# Sheet1.net
KiCad netlist of a schematic drawn in Altium Designer
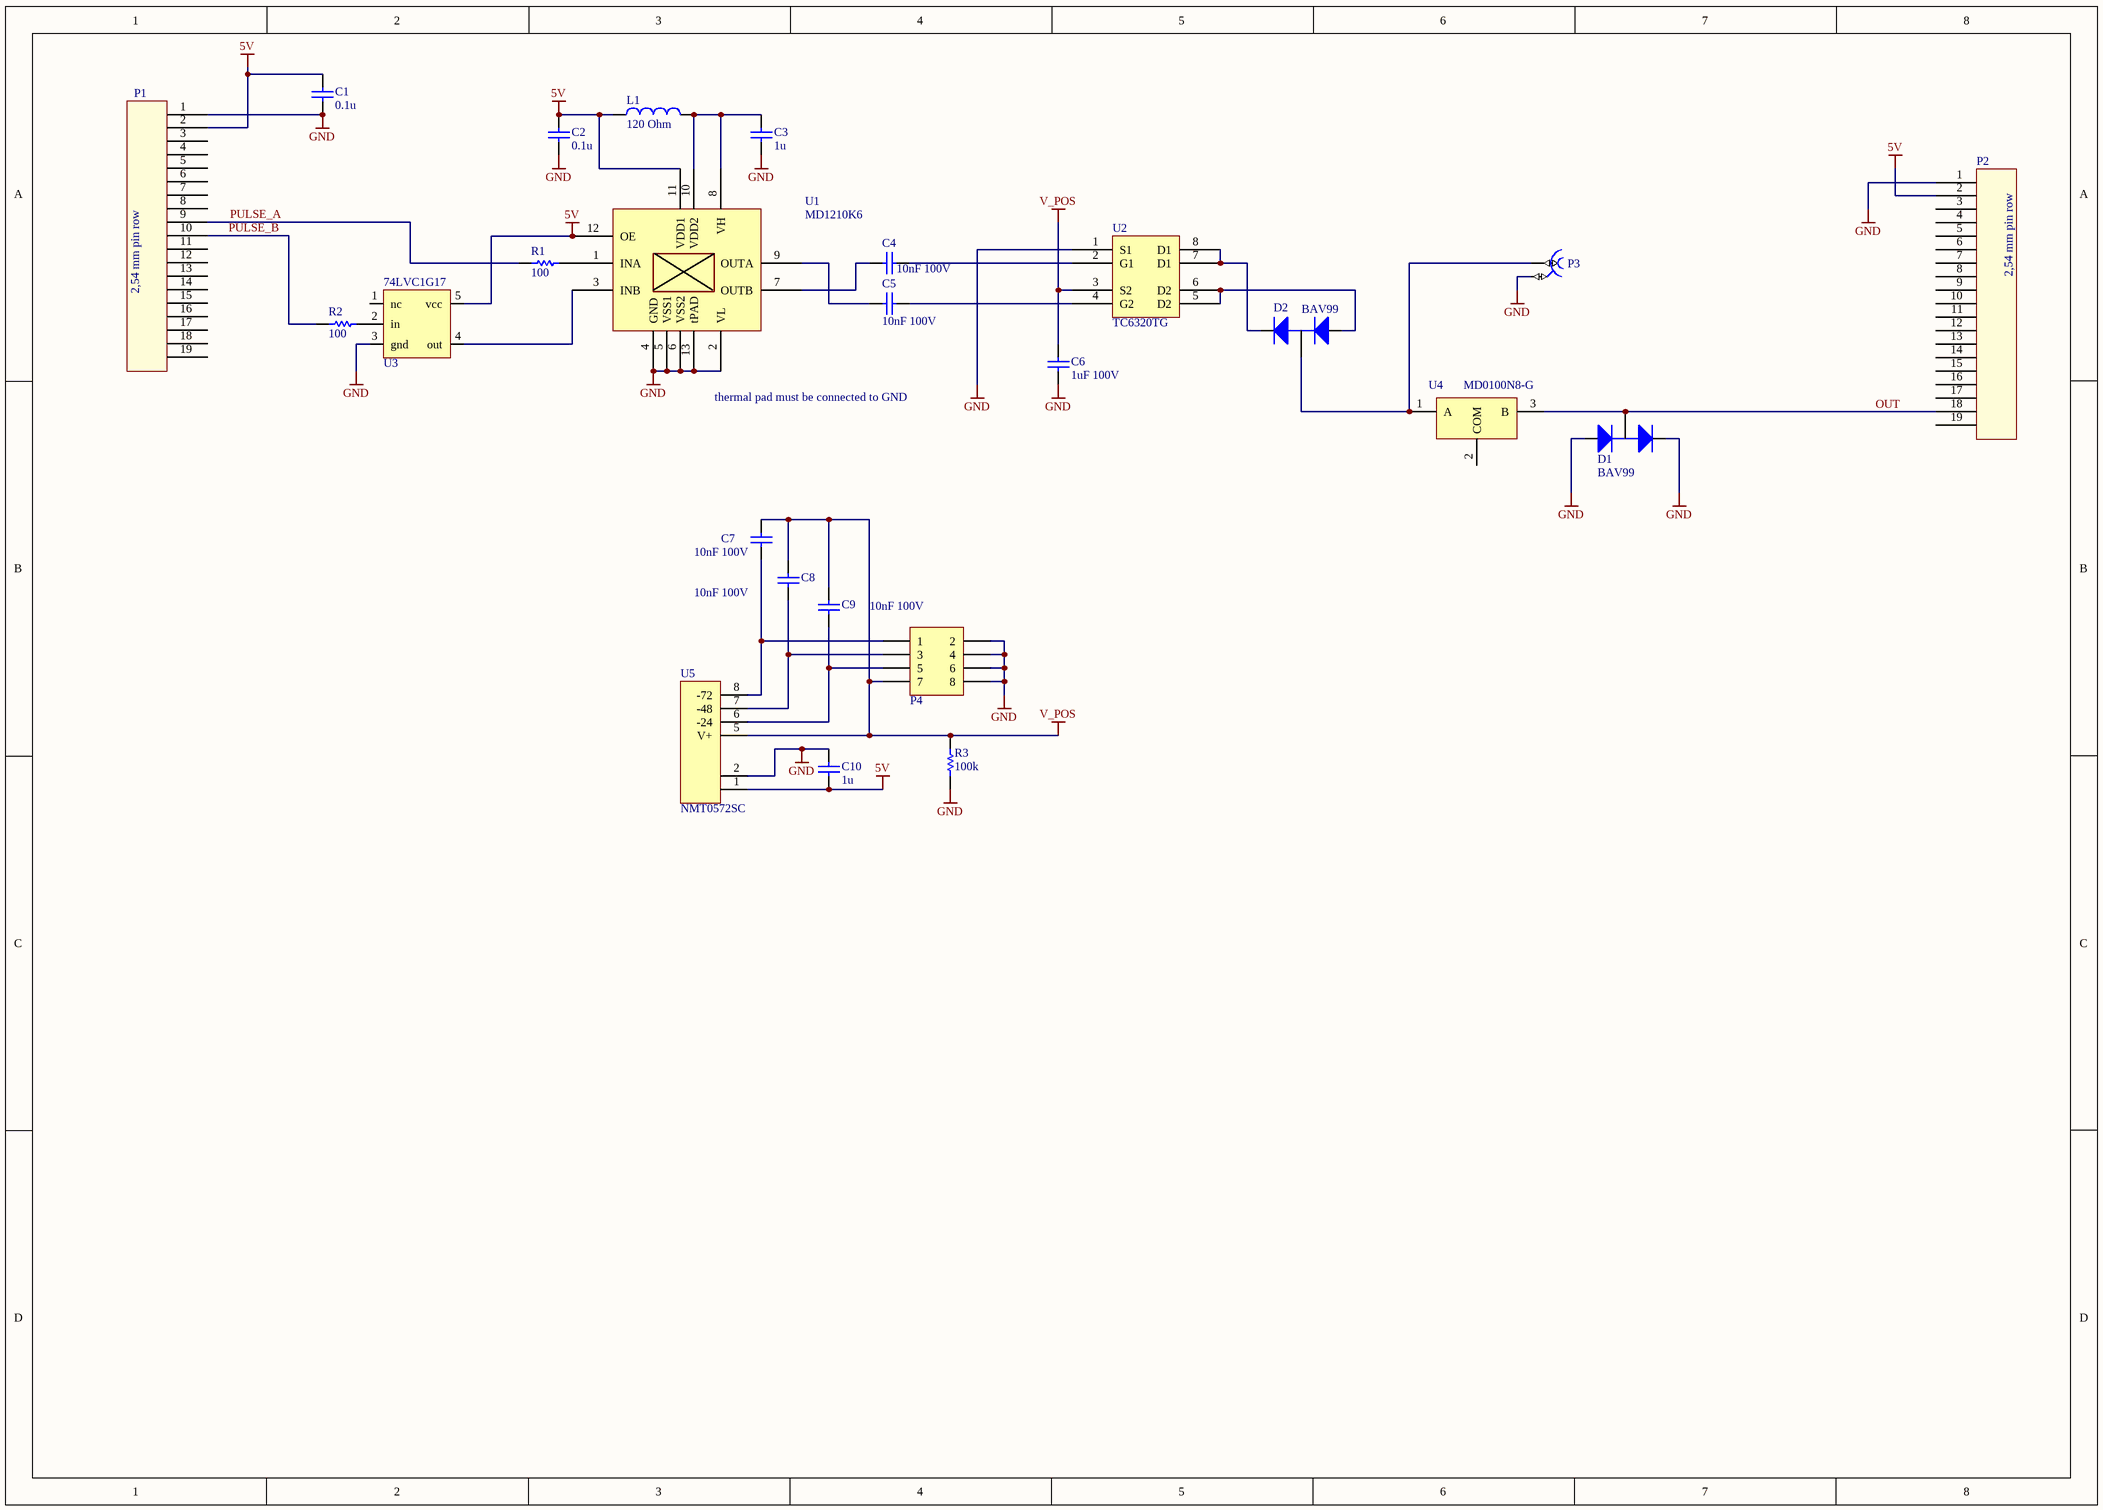
[diagram p0: Sheet1.SchDoc]

(export (version "E")
  (design (tool "Eeschema 10.0.6"))
  (components
    (comp (ref "C1")
      (value "0.1u")
      (footprint "0603RC")
      (description "Capacitor")
      (fields (field (name "PUBLISHER") "Altium Limited"))
      (libsource (lib "Miscellaneous Devices") (part "Cap"))
    )
    (comp (ref "C2")
      (value "0.1u")
      (footprint "0603RC")
      (description "Capacitor")
      (fields (field (name "PUBLISHER") "Altium Limited"))
      (libsource (lib "Miscellaneous Devices") (part "Cap"))
    )
    (comp (ref "C3")
      (value "1u")
      (footprint "0805RC")
      (description "Capacitor")
      (fields (field (name "PUBLISHER") "Altium Limited"))
      (libsource (lib "Miscellaneous Devices") (part "Cap"))
    )
    (comp (ref "C4")
      (value "10nF 100V")
      (footprint "0805RC")
      (description "Capacitor")
      (fields (field (name "PUBLISHER") "Altium Limited"))
      (libsource (lib "Miscellaneous Devices") (part "Cap"))
    )
    (comp (ref "C5")
      (value "10nF 100V")
      (footprint "0805RC")
      (description "Capacitor")
      (fields (field (name "PUBLISHER") "Altium Limited"))
      (libsource (lib "Miscellaneous Devices") (part "Cap"))
    )
    (comp (ref "C6")
      (value "1uF 100V")
      (footprint "1206RC")
      (description "Capacitor")
      (fields (field (name "PUBLISHER") "Altium Limited"))
      (libsource (lib "Miscellaneous Devices") (part "Cap"))
    )
    (comp (ref "C7")
      (value "10nF 100V")
      (footprint "0805RC")
      (description "Capacitor")
      (fields (field (name "PUBLISHER") "Altium Limited"))
      (libsource (lib "Miscellaneous Devices") (part "Cap"))
    )
    (comp (ref "C8")
      (value "10nF 100V")
      (footprint "0805RC")
      (description "Capacitor")
      (fields (field (name "PUBLISHER") "Altium Limited"))
      (libsource (lib "Miscellaneous Devices") (part "Cap"))
    )
    (comp (ref "C9")
      (value "10nF 100V")
      (footprint "0805RC")
      (description "Capacitor")
      (fields (field (name "PUBLISHER") "Altium Limited"))
      (libsource (lib "Miscellaneous Devices") (part "Cap"))
    )
    (comp (ref "C10")
      (value "1u")
      (footprint "0805RC")
      (description "Capacitor")
      (fields (field (name "PUBLISHER") "Altium Limited"))
      (libsource (lib "Miscellaneous Devices") (part "Cap"))
    )
    (comp (ref "D1")
      (value "BAV99")
      (footprint "SOT-23")
      (description "Medium-speed Switching Double Diode with Low Leakage Current")
      (fields (field (name "PUBLISHER") "Altium Limited"))
      (libsource (lib "Miscellaneous Devices") (part "BAV199"))
    )
    (comp (ref "D2")
      (value "BAV99")
      (footprint "SOT-23")
      (description "Medium-speed Switching Double Diode with Low Leakage Current")
      (fields (field (name "PUBLISHER") "Altium Limited"))
      (libsource (lib "Miscellaneous Devices") (part "BAV199"))
    )
    (comp (ref "L1")
      (value "120 Ohm")
      (footprint "0805R")
      (description "Inductor")
      (fields (field (name "Comment") "BLM21PG121SN1D") (field (name "PUBLISHER") "Altium Limited"))
      (libsource (lib "Miscellaneous Devices") (part "Inductor"))
    )
    (comp (ref "P1")
      (value "PLS_2.54mm-19")
      (footprint "PLS_2.54mm-19")
      (libsource (lib "") (part "PLS_2.54mm-19_1"))
    )
    (comp (ref "P2")
      (value "PLS_2.54mm-19")
      (footprint "PLS_2.54mm-19")
      (libsource (lib "alt_vovan") (part "PLS_2.54mm-19"))
    )
    (comp (ref "P3")
      (value "SMA")
      (footprint "echOpen_ADC_Card:AMPHENOL_132357-11")
      (fields
        (field (name "PART NUMBER") "AMPHENOL_132357-11")
        (field (name "MANUFACTURER") "AMPHENOL")
        (field (name "MANUFACTURER PART NUMBER") "132357-11")
        (field (name "AUTHOR") "CERN DEM JLC")
      )
      (libsource (lib "Sof-Connectors") (part "Coax_1Female_1Shield"))
    )
    (comp (ref "P4")
      (value "PLD-8")
      (footprint "PLD-8")
      (description "Header, 4-Pin, Dual row")
      (fields (field (name "PUBLISHER") "Altium Limited"))
      (libsource (lib "Miscellaneous Devices") (part "Header 4X2"))
    )
    (comp (ref "R1")
      (value "100")
      (footprint "0603R")
      (description "Resistor")
      (fields (field (name "PUBLISHER") "Altium Limited"))
      (libsource (lib "Miscellaneous Devices") (part "Res1"))
    )
    (comp (ref "R2")
      (value "100")
      (footprint "0603R")
      (description "Resistor")
      (fields (field (name "PUBLISHER") "Altium Limited"))
      (libsource (lib "Miscellaneous Devices") (part "Res1"))
    )
    (comp (ref "R3")
      (value "100k")
      (footprint "0805R")
      (description "Resistor")
      (fields (field (name "PUBLISHER") "Altium Limited"))
      (libsource (lib "Miscellaneous Devices") (part "Res1"))
    )
    (comp (ref "U1") (value "MD1210K6") (footprint "QFN-12 4x4mm") (libsource (lib "Pulser") (part "MD1210")))
    (comp (ref "U2")
      (value "TC6320TG")
      (footprint "SOIC127P600-8N")
      (description "N- and P-Channel  Enhancement-Mode MOSFET Pair")
      (libsource (lib "Pulser") (part "TC6320"))
    )
    (comp (ref "U3")
      (value "74LVC1G17")
      (footprint "SOT-23_5")
      (description "shmitt trigger sot23-5")
      (libsource (lib "alt2017") (part "74LVC1G17"))
    )
    (comp (ref "U4")
      (value "MD0100N8-G")
      (footprint "echOpen_ADC_Card:SOT89")
      (description "3-Ultra-Sound HV Switch 1=A 2=COM 3=B")
      (fields (field (name "MANUFACTURER") "Supertex inc.") (field (name "AUTHOR") "S. Jafar"))
      (libsource (lib "Sof-ICs And Semiconductors") (part "MD0100"))
    )
    (comp (ref "U5")
      (value "NMT0572SC")
      (footprint "NMT0572SC")
      (description "Horizontal")
      (fields (field (name "PUBLISHER") "Altium Limited"))
      (libsource (lib "Miscellaneous Devices") (part "Header 8"))
    )
  )
  (nets
    (net (code "2") (name "/PULSE_A") (class "Default")
      (node (ref "P1") (pin "9") (pinfunction "9_9") (pintype "passive"))
      (node (ref "R1") (pin "1") (pinfunction "1_1") (pintype "passive"))
    )
    (net (code "3") (name "/PULSE_B") (class "Default")
      (node (ref "P1") (pin "10") (pinfunction "10_10") (pintype "passive"))
      (node (ref "R2") (pin "1") (pinfunction "1_1") (pintype "passive"))
    )
    (net (code "4") (name "5V") (class "Default")
      (node (ref "C1") (pin "2") (pinfunction "2_2") (pintype "passive"))
      (node (ref "C10") (pin "1") (pinfunction "1_1") (pintype "passive"))
      (node (ref "C2") (pin "2") (pinfunction "2_2") (pintype "passive"))
      (node (ref "L1") (pin "1") (pinfunction "1_1") (pintype "passive"))
      (node (ref "P1") (pin "2") (pinfunction "2_2") (pintype "passive"))
      (node (ref "P2") (pin "2") (pinfunction "2_2") (pintype "passive"))
      (node (ref "U1") (pin "11") (pinfunction "VDD1_11") (pintype "passive"))
      (node (ref "U1") (pin "12") (pinfunction "OE_12") (pintype "passive"))
      (node (ref "U3") (pin "5") (pinfunction "vcc_5") (pintype "passive"))
      (node (ref "U5") (pin "1") (pinfunction "1_1") (pintype "passive"))
    )
    (net (code "5") (name "GND") (class "Default")
      (node (ref "C1") (pin "1") (pinfunction "1_1") (pintype "passive"))
      (node (ref "C10") (pin "2") (pinfunction "2_2") (pintype "passive"))
      (node (ref "C2") (pin "1") (pinfunction "1_1") (pintype "passive"))
      (node (ref "C3") (pin "1") (pinfunction "1_1") (pintype "passive"))
      (node (ref "C6") (pin "1") (pinfunction "1_1") (pintype "passive"))
      (node (ref "D1") (pin "1") (pinfunction "A_1") (pintype "passive"))
      (node (ref "D1") (pin "2") (pinfunction "K_2") (pintype "passive"))
      (node (ref "P1") (pin "1") (pinfunction "1_1") (pintype "passive"))
      (node (ref "P2") (pin "1") (pinfunction "1_1") (pintype "passive"))
      (node (ref "P3") (pin "2") (pinfunction "2_2") (pintype "bidirectional"))
      (node (ref "P4") (pin "2") (pinfunction "2_2") (pintype "passive"))
      (node (ref "P4") (pin "4") (pinfunction "4_4") (pintype "passive"))
      (node (ref "P4") (pin "6") (pinfunction "6_6") (pintype "passive"))
      (node (ref "P4") (pin "8") (pinfunction "8_8") (pintype "passive"))
      (node (ref "R3") (pin "1") (pinfunction "1_1") (pintype "passive"))
      (node (ref "U1") (pin "13") (pinfunction "tPAD_13") (pintype "passive"))
      (node (ref "U1") (pin "2") (pinfunction "VL_2") (pintype "passive"))
      (node (ref "U1") (pin "4") (pinfunction "GND_4") (pintype "passive"))
      (node (ref "U1") (pin "5") (pinfunction "VSS1_5") (pintype "passive"))
      (node (ref "U1") (pin "6") (pinfunction "VSS2_6") (pintype "passive"))
      (node (ref "U2") (pin "1") (pinfunction "S1_1") (pintype "passive"))
      (node (ref "U3") (pin "3") (pinfunction "gnd_3") (pintype "passive"))
      (node (ref "U5") (pin "2") (pinfunction "2_2") (pintype "passive"))
    )
    (net (code "6") (name "Net-(D1-C)") (class "Default")
      (node (ref "D1") (pin "3") (pinfunction "C_3") (pintype "passive"))
      (node (ref "P2") (pin "18") (pinfunction "18_18") (pintype "passive"))
      (node (ref "U4") (pin "3") (pinfunction "B_3") (pintype "passive"))
    )
    (net (code "7") (name "Net-(D2-A)") (class "Default")
      (node (ref "D2") (pin "1") (pinfunction "A_1") (pintype "passive"))
      (node (ref "U2") (pin "5") (pinfunction "D2_5") (pintype "passive"))
      (node (ref "U2") (pin "6") (pinfunction "D2_6") (pintype "passive"))
    )
    (net (code "8") (name "Net-(D2-C)") (class "Default")
      (node (ref "D2") (pin "3") (pinfunction "C_3") (pintype "passive"))
      (node (ref "P3") (pin "1") (pinfunction "1_1") (pintype "bidirectional"))
      (node (ref "U4") (pin "1") (pinfunction "A_1") (pintype "passive"))
    )
    (net (code "9") (name "Net-(D2-K)") (class "Default")
      (node (ref "D2") (pin "2") (pinfunction "K_2") (pintype "passive"))
      (node (ref "U2") (pin "7") (pinfunction "D1_7") (pintype "passive"))
      (node (ref "U2") (pin "8") (pinfunction "D1_8") (pintype "passive"))
    )
    (net (code "10") (name "Net-(U1-INA)") (class "Default")
      (node (ref "R1") (pin "2") (pinfunction "2_2") (pintype "passive"))
      (node (ref "U1") (pin "1") (pinfunction "INA_1") (pintype "passive"))
    )
    (net (code "11") (name "Net-(U1-INB)") (class "Default")
      (node (ref "U1") (pin "3") (pinfunction "INB_3") (pintype "passive"))
      (node (ref "U3") (pin "4") (pinfunction "out_4") (pintype "passive"))
    )
    (net (code "12") (name "Net-(U1-OUTA)") (class "Default")
      (node (ref "C5") (pin "2") (pinfunction "2_2") (pintype "passive"))
      (node (ref "U1") (pin "9") (pinfunction "OUTA_9") (pintype "passive"))
    )
    (net (code "13") (name "Net-(U1-OUTB)") (class "Default")
      (node (ref "C4") (pin "2") (pinfunction "2_2") (pintype "passive"))
      (node (ref "U1") (pin "7") (pinfunction "OUTB_7") (pintype "passive"))
    )
    (net (code "14") (name "Net-(U1-VDD2)") (class "Default")
      (node (ref "C3") (pin "2") (pinfunction "2_2") (pintype "passive"))
      (node (ref "L1") (pin "2") (pinfunction "2_2") (pintype "passive"))
      (node (ref "U1") (pin "10") (pinfunction "VDD2_10") (pintype "passive"))
      (node (ref "U1") (pin "8") (pinfunction "VH_8") (pintype "passive"))
    )
    (net (code "15") (name "Net-(U2-G1)") (class "Default")
      (node (ref "C4") (pin "1") (pinfunction "1_1") (pintype "passive"))
      (node (ref "U2") (pin "2") (pinfunction "G1_2") (pintype "passive"))
    )
    (net (code "16") (name "Net-(U2-G2)") (class "Default")
      (node (ref "C5") (pin "1") (pinfunction "1_1") (pintype "passive"))
      (node (ref "U2") (pin "4") (pinfunction "G2_4") (pintype "passive"))
    )
    (net (code "17") (name "Net-(U3-in)") (class "Default")
      (node (ref "R2") (pin "2") (pinfunction "2_2") (pintype "passive"))
      (node (ref "U3") (pin "2") (pinfunction "in_2") (pintype "passive"))
    )
    (net (code "18") (name "Net-(U5--24)") (class "Default")
      (node (ref "C9") (pin "2") (pinfunction "2_2") (pintype "passive"))
      (node (ref "P4") (pin "5") (pinfunction "5_5") (pintype "passive"))
      (node (ref "U5") (pin "6") (pinfunction "-24_6") (pintype "passive"))
    )
    (net (code "19") (name "Net-(U5--48)") (class "Default")
      (node (ref "C8") (pin "2") (pinfunction "2_2") (pintype "passive"))
      (node (ref "P4") (pin "3") (pinfunction "3_3") (pintype "passive"))
      (node (ref "U5") (pin "7") (pinfunction "-48_7") (pintype "passive"))
    )
    (net (code "20") (name "Net-(U5--72)") (class "Default")
      (node (ref "C7") (pin "2") (pinfunction "2_2") (pintype "passive"))
      (node (ref "P4") (pin "1") (pinfunction "1_1") (pintype "passive"))
      (node (ref "U5") (pin "8") (pinfunction "-72_8") (pintype "passive"))
    )
    (net (code "21") (name "V_POS") (class "Default")
      (node (ref "C6") (pin "2") (pinfunction "2_2") (pintype "passive"))
      (node (ref "C7") (pin "1") (pinfunction "1_1") (pintype "passive"))
      (node (ref "C8") (pin "1") (pinfunction "1_1") (pintype "passive"))
      (node (ref "C9") (pin "1") (pinfunction "1_1") (pintype "passive"))
      (node (ref "P4") (pin "7") (pinfunction "7_7") (pintype "passive"))
      (node (ref "R3") (pin "2") (pinfunction "2_2") (pintype "passive"))
      (node (ref "U2") (pin "3") (pinfunction "S2_3") (pintype "passive"))
      (node (ref "U5") (pin "5") (pinfunction "V+_5") (pintype "passive"))
    )
    (net (code "22") (name "unconnected-(P1-Pad3)") (class "Default")
      (node (ref "P1") (pin "3") (pinfunction "3_3") (pintype "passive"))
    )
    (net (code "23") (name "unconnected-(P1-Pad4)") (class "Default")
      (node (ref "P1") (pin "4") (pinfunction "4_4") (pintype "passive"))
    )
    (net (code "24") (name "unconnected-(P1-Pad5)") (class "Default")
      (node (ref "P1") (pin "5") (pinfunction "5_5") (pintype "passive"))
    )
    (net (code "25") (name "unconnected-(P1-Pad6)") (class "Default")
      (node (ref "P1") (pin "6") (pinfunction "6_6") (pintype "passive"))
    )
    (net (code "26") (name "unconnected-(P1-Pad7)") (class "Default")
      (node (ref "P1") (pin "7") (pinfunction "7_7") (pintype "passive"))
    )
    (net (code "27") (name "unconnected-(P1-Pad8)") (class "Default")
      (node (ref "P1") (pin "8") (pinfunction "8_8") (pintype "passive"))
    )
    (net (code "28") (name "unconnected-(P1-Pad11)") (class "Default")
      (node (ref "P1") (pin "11") (pinfunction "11_11") (pintype "passive"))
    )
    (net (code "29") (name "unconnected-(P1-Pad12)") (class "Default")
      (node (ref "P1") (pin "12") (pinfunction "12_12") (pintype "passive"))
    )
    (net (code "30") (name "unconnected-(P1-Pad13)") (class "Default")
      (node (ref "P1") (pin "13") (pinfunction "13_13") (pintype "passive"))
    )
    (net (code "31") (name "unconnected-(P1-Pad14)") (class "Default")
      (node (ref "P1") (pin "14") (pinfunction "14_14") (pintype "passive"))
    )
    (net (code "32") (name "unconnected-(P1-Pad15)") (class "Default")
      (node (ref "P1") (pin "15") (pinfunction "15_15") (pintype "passive"))
    )
    (net (code "33") (name "unconnected-(P1-Pad16)") (class "Default")
      (node (ref "P1") (pin "16") (pinfunction "16_16") (pintype "passive"))
    )
    (net (code "34") (name "unconnected-(P1-Pad17)") (class "Default")
      (node (ref "P1") (pin "17") (pinfunction "17_17") (pintype "passive"))
    )
    (net (code "35") (name "unconnected-(P1-Pad18)") (class "Default")
      (node (ref "P1") (pin "18") (pinfunction "18_18") (pintype "passive"))
    )
    (net (code "36") (name "unconnected-(P1-Pad19)") (class "Default")
      (node (ref "P1") (pin "19") (pinfunction "19_19") (pintype "passive"))
    )
    (net (code "37") (name "unconnected-(P2-Pad3)") (class "Default")
      (node (ref "P2") (pin "3") (pinfunction "3_3") (pintype "passive"))
    )
    (net (code "38") (name "unconnected-(P2-Pad4)") (class "Default")
      (node (ref "P2") (pin "4") (pinfunction "4_4") (pintype "passive"))
    )
    (net (code "39") (name "unconnected-(P2-Pad5)") (class "Default")
      (node (ref "P2") (pin "5") (pinfunction "5_5") (pintype "passive"))
    )
    (net (code "40") (name "unconnected-(P2-Pad6)") (class "Default")
      (node (ref "P2") (pin "6") (pinfunction "6_6") (pintype "passive"))
    )
    (net (code "41") (name "unconnected-(P2-Pad7)") (class "Default")
      (node (ref "P2") (pin "7") (pinfunction "7_7") (pintype "passive"))
    )
    (net (code "42") (name "unconnected-(P2-Pad8)") (class "Default")
      (node (ref "P2") (pin "8") (pinfunction "8_8") (pintype "passive"))
    )
    (net (code "43") (name "unconnected-(P2-Pad9)") (class "Default")
      (node (ref "P2") (pin "9") (pinfunction "9_9") (pintype "passive"))
    )
    (net (code "44") (name "unconnected-(P2-Pad10)") (class "Default")
      (node (ref "P2") (pin "10") (pinfunction "10_10") (pintype "passive"))
    )
    (net (code "45") (name "unconnected-(P2-Pad11)") (class "Default")
      (node (ref "P2") (pin "11") (pinfunction "11_11") (pintype "passive"))
    )
    (net (code "46") (name "unconnected-(P2-Pad12)") (class "Default")
      (node (ref "P2") (pin "12") (pinfunction "12_12") (pintype "passive"))
    )
    (net (code "47") (name "unconnected-(P2-Pad13)") (class "Default")
      (node (ref "P2") (pin "13") (pinfunction "13_13") (pintype "passive"))
    )
    (net (code "48") (name "unconnected-(P2-Pad14)") (class "Default")
      (node (ref "P2") (pin "14") (pinfunction "14_14") (pintype "passive"))
    )
    (net (code "49") (name "unconnected-(P2-Pad15)") (class "Default")
      (node (ref "P2") (pin "15") (pinfunction "15_15") (pintype "passive"))
    )
    (net (code "50") (name "unconnected-(P2-Pad16)") (class "Default")
      (node (ref "P2") (pin "16") (pinfunction "16_16") (pintype "passive"))
    )
    (net (code "51") (name "unconnected-(P2-Pad17)") (class "Default")
      (node (ref "P2") (pin "17") (pinfunction "17_17") (pintype "passive"))
    )
    (net (code "52") (name "unconnected-(P2-Pad19)") (class "Default")
      (node (ref "P2") (pin "19") (pinfunction "19_19") (pintype "passive"))
    )
    (net (code "53") (name "unconnected-(U3-nc-Pad1)") (class "Default")
      (node (ref "U3") (pin "1") (pinfunction "nc_1") (pintype "passive"))
    )
    (net (code "54") (name "unconnected-(U4-COM-Pad2)") (class "Default")
      (node (ref "U4") (pin "2") (pinfunction "COM_2") (pintype "passive"))
    )
    (net (code "55") (name "unconnected-(U5-Pad3)") (class "Default")
      (node (ref "U5") (pin "3") (pinfunction "3_3") (pintype "passive"))
    )
    (net (code "56") (name "unconnected-(U5-Pad4)") (class "Default")
      (node (ref "U5") (pin "4") (pinfunction "4_4") (pintype "passive"))
    )
  )
)
